# Sheet1.net
KiCad netlist of a schematic drawn in Altium Designer
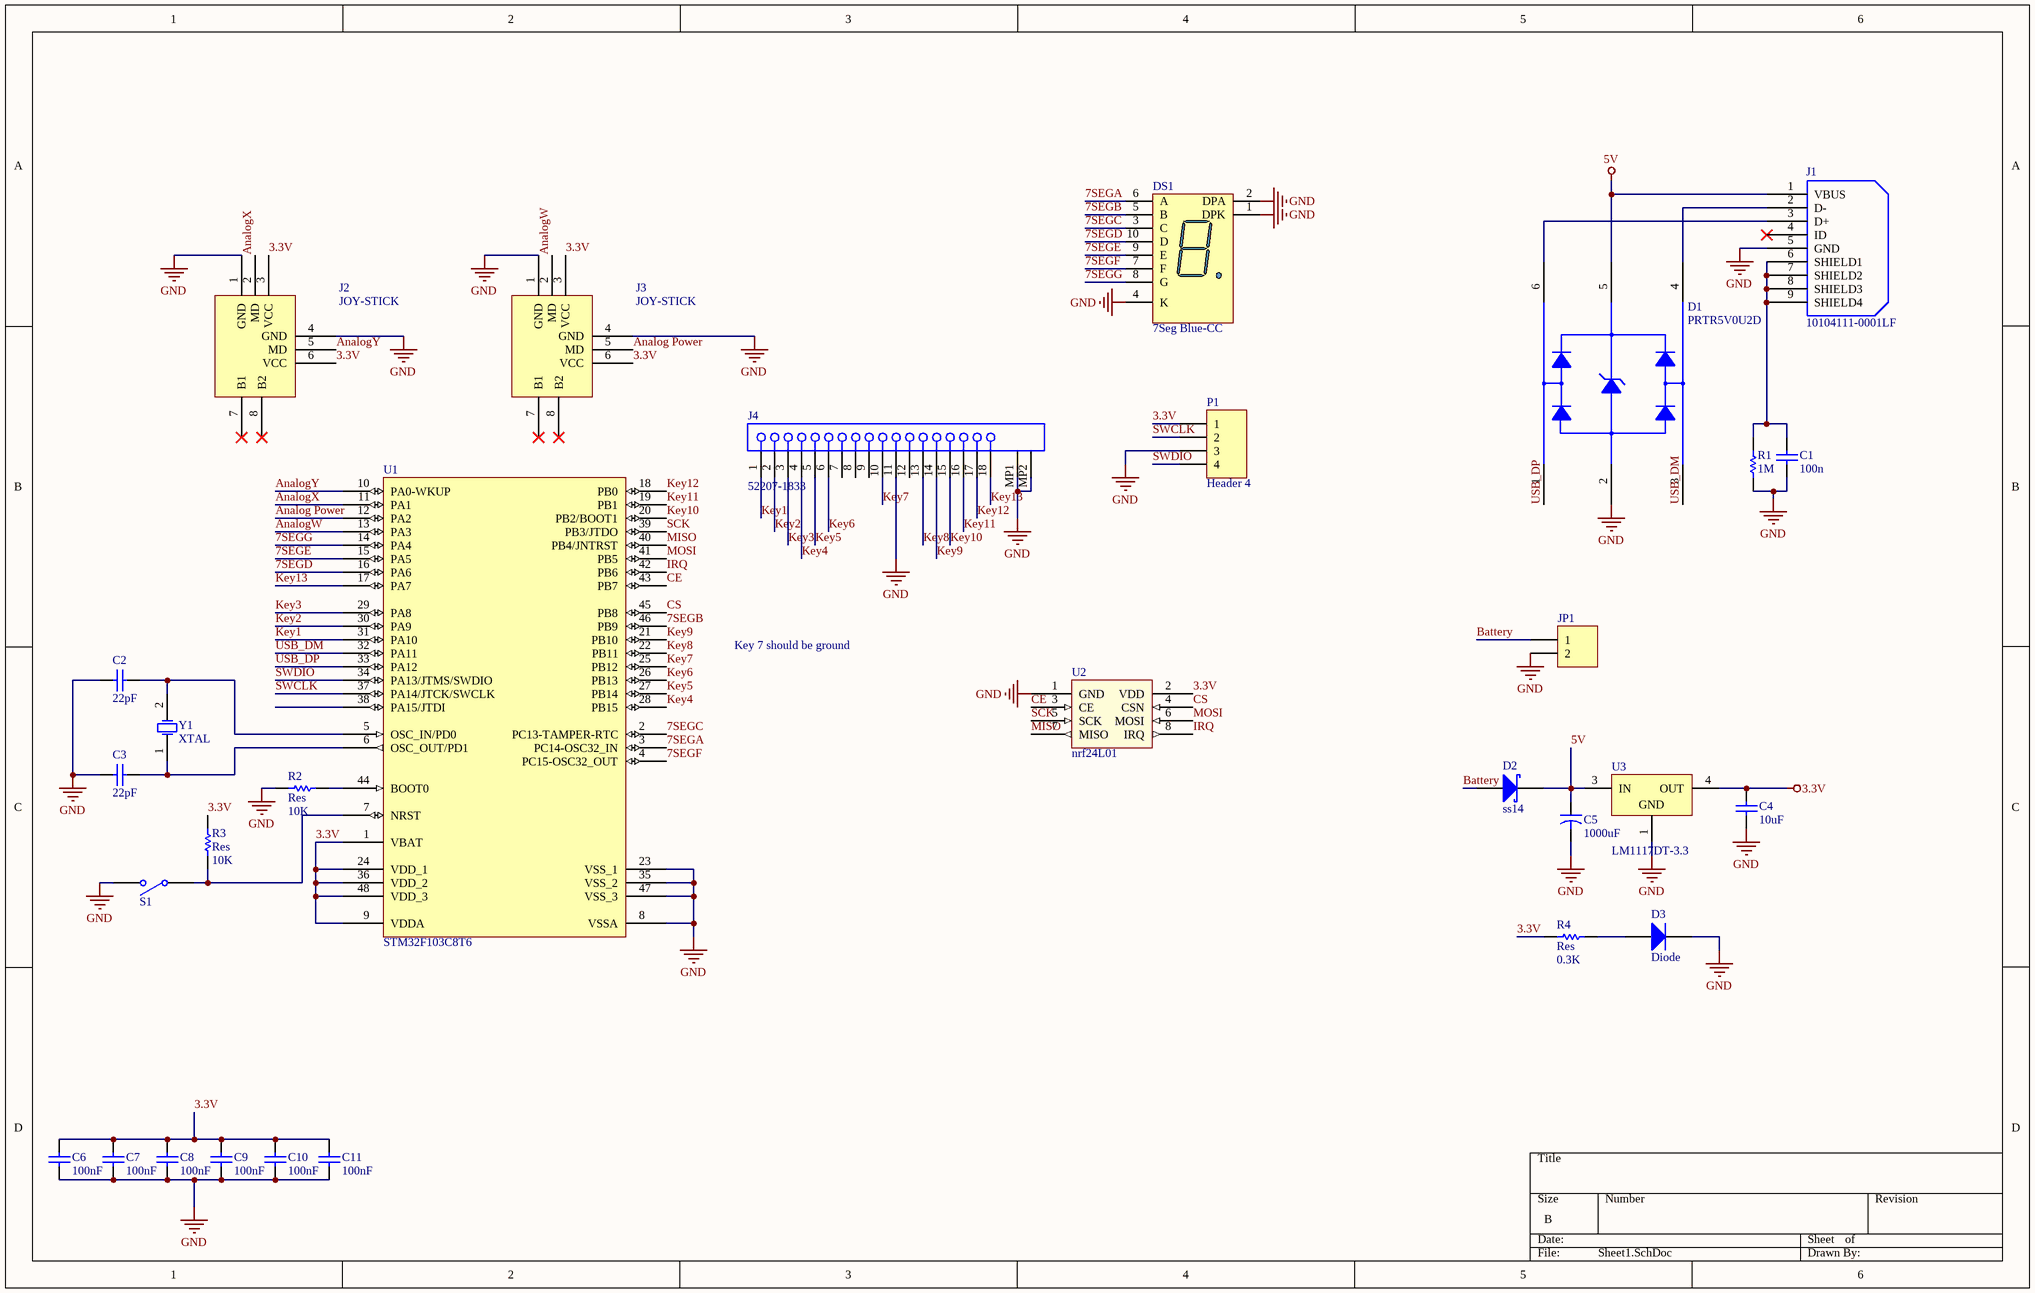
[diagram p0: Sheet1.SchDoc]

(export (version "E")
  (design (tool "Eeschema 10.0.6"))
  (components
    (comp (ref "C1")
      (value "100n")
      (footprint "6-0805_N")
      (description "Capacitor")
      (fields (field (name "PUBLISHER") "Altium Limited"))
      (libsource (lib "Miscellaneous Devices") (part "Cap"))
    )
    (comp (ref "C2")
      (value "22pF")
      (footprint "2012[0805]")
      (description "Capacitor")
      (fields (field (name "Comment") "Cap_UP") (field (name "PUBLISHER") "Altium Limited"))
      (libsource (lib "KN2CLib") (part "Cap_UP"))
    )
    (comp (ref "C3")
      (value "22pF")
      (footprint "2012[0805]")
      (description "Capacitor")
      (fields (field (name "Comment") "Cap_UP") (field (name "PUBLISHER") "Altium Limited"))
      (libsource (lib "KN2CLib") (part "Cap_UP"))
    )
    (comp (ref "C4")
      (value "10uF")
      (footprint "2012[0805]")
      (description "Capacitor")
      (fields (field (name "Comment") "Cap_UP") (field (name "PUBLISHER") "Altium Limited"))
      (libsource (lib "KN2CLib") (part "Cap_UP"))
    )
    (comp (ref "C5")
      (value "1000uF")
      (footprint "7343")
      (description "Capacitor")
      (fields (field (name "Comment") "Cap_El") (field (name "PUBLISHER") "Altium Limited"))
      (libsource (lib "KN2CLib") (part "Cap_El"))
    )
    (comp (ref "C6")
      (value "100nF")
      (footprint "2012[0805]")
      (description "Capacitor")
      (fields (field (name "Comment") "Cap_UP") (field (name "PUBLISHER") "Altium Limited"))
      (libsource (lib "KN2CLib") (part "Cap_UP"))
    )
    (comp (ref "C7")
      (value "100nF")
      (footprint "2012[0805]")
      (description "Capacitor")
      (fields (field (name "Comment") "Cap_UP") (field (name "PUBLISHER") "Altium Limited"))
      (libsource (lib "KN2CLib") (part "Cap_UP"))
    )
    (comp (ref "C8")
      (value "100nF")
      (footprint "2012[0805]")
      (description "Capacitor")
      (fields (field (name "Comment") "Cap_UP") (field (name "PUBLISHER") "Altium Limited"))
      (libsource (lib "KN2CLib") (part "Cap_UP"))
    )
    (comp (ref "C9")
      (value "100nF")
      (footprint "2012[0805]")
      (description "Capacitor")
      (fields (field (name "Comment") "Cap_UP") (field (name "PUBLISHER") "Altium Limited"))
      (libsource (lib "KN2CLib") (part "Cap_UP"))
    )
    (comp (ref "C10")
      (value "100nF")
      (footprint "2012[0805]")
      (description "Capacitor")
      (fields (field (name "Comment") "Cap_UP") (field (name "PUBLISHER") "Altium Limited"))
      (libsource (lib "KN2CLib") (part "Cap_UP"))
    )
    (comp (ref "C11")
      (value "100nF")
      (footprint "2012[0805]")
      (description "Capacitor")
      (fields (field (name "Comment") "Cap_UP") (field (name "PUBLISHER") "Altium Limited"))
      (libsource (lib "KN2CLib") (part "Cap_UP"))
    )
    (comp (ref "D1")
      (value "PRTR5V0U2D")
      (footprint "PRTR5V0U2D")
      (description "Double rail-to-rail USB ESD protection diode")
      (fields (field (name "MANUFACTURER") "Philips") (field (name "MPN") "PRTR5V0U2X"))
      (libsource (lib "KN2CLib") (part "PRTR5V0U2D"))
    )
    (comp (ref "D2")
      (value "ss14")
      (footprint "US1m")
      (description "Schottky Diode")
      (fields (field (name "PUBLISHER") "Altium Limited"))
      (libsource (lib "Miscellaneous Devices") (part "D Schottky"))
    )
    (comp (ref "D3")
      (value "Diode")
      (footprint "2012[0805]")
      (description "1 Amp General Purpose Rectifier")
      (fields (field (name "PUBLISHER") "Altium Limited"))
      (libsource (lib "KN2CLib") (part "Diode"))
    )
    (comp (ref "DS1")
      (value "7Seg Blue-CC")
      (footprint "7Segment Small")
      (description "14.2 mm General Purpose Blue 7-Segment Display: CC, RH DP, Gray Surface")
      (fields (field (name "PUBLISHER") "Altium Limited"))
      (libsource (lib "KN2CLib") (part "7Seg Blue-CC_1"))
    )
    (comp (ref "J1")
      (value "10104111-0001LF")
      (footprint "USB_MINI")
      (description "Micro USB AB Connector")
      (fields (field (name "MANUFACTURER") "FCI") (field (name "Comment") "USB_AB"))
      (libsource (lib "KN2CLib") (part "USB_AB"))
    )
    (comp (ref "J2")
      (value "JOY-STICK")
      (footprint "JOY STICK")
      (libsource (lib "KN2CLib") (part "JOY STICK"))
    )
    (comp (ref "J3")
      (value "JOY-STICK")
      (footprint "JOY STICK")
      (libsource (lib "KN2CLib") (part "JOY STICK"))
    )
    (comp (ref "J4")
      (value "52207-1833")
      (footprint "MOLX-52207-1833")
      (fields (field (name "MANUFACTURER") "Molex"))
      (libsource (lib "Molex FFC - FPC Connectors (SMT)") (part "52207-1833"))
    )
    (comp (ref "JP1")
      (value "Header 2")
      (footprint "HDR1X2A")
      (description "Header, 2-Pin")
      (fields (field (name "PUBLISHER") "Altium Limited"))
      (libsource (lib "KN2CLib") (part "Header 2"))
    )
    (comp (ref "P1")
      (value "Header 4")
      (footprint "HDR1X4")
      (description "Header, 4-Pin")
      (fields (field (name "PUBLISHER") "Altium Limited"))
      (libsource (lib "Miscellaneous Connectors") (part "Header 4"))
    )
    (comp (ref "R1")
      (value "1M")
      (footprint "2012[0805]")
      (description "Semiconductor Resistor")
      (fields (field (name "PUBLISHER") "Altium Limited"))
      (libsource (lib "KN2CLib") (part "Res"))
    )
    (comp (ref "R2")
      (value "Res")
      (footprint "2012[0805]")
      (description "Semiconductor Resistor")
      (fields (field (name "ALTIUM_VALUE") "10K") (field (name "PUBLISHER") "Altium Limited"))
      (libsource (lib "KN2CLib") (part "Res"))
    )
    (comp (ref "R3")
      (value "Res")
      (footprint "2012[0805]")
      (description "Semiconductor Resistor")
      (fields (field (name "ALTIUM_VALUE") "10K") (field (name "PUBLISHER") "Altium Limited"))
      (libsource (lib "KN2CLib") (part "Res"))
    )
    (comp (ref "R4")
      (value "Res")
      (footprint "2012[0805]")
      (description "Semiconductor Resistor")
      (fields (field (name "ALTIUM_VALUE") "0.3K") (field (name "PUBLISHER") "Altium Limited"))
      (libsource (lib "KN2CLib") (part "Res"))
    )
    (comp (ref "S1")
      (value "SW-SPST")
      (footprint "SW-SMD")
      (description "Single-Pole, Single-Throw Switch")
      (fields (field (name "PUBLISHER") "Altium Limited"))
      (libsource (lib "KN2CLib") (part "SW-SPST"))
    )
    (comp (ref "U1")
      (value "STM32F103C8T6")
      (footprint "LQFP48_N")
      (description "STM32 ARM-based 32-bit MCU with 64 Kbytes Flash, 48-pin LQFP, Industrial Temperature")
      (fields (field (name "PUBLISHER") "Altium Limited"))
      (libsource (lib "ST Microcontroller 32-Bit STM32") (part "STM32F103C8T6"))
    )
    (comp (ref "U2") (value "nrf24L01") (footprint "NRF24L01") (libsource (lib "KN2CLib") (part "nrf24L01")))
    (comp (ref "U3")
      (value "LM1117DT-3.3")
      (footprint "SOT223")
      (description "800mA Low-Dropout Linear Regulator, 3-pin TO-252")
      (fields
        (field (name "MANUFACTURER") "National Semiconductor")
        (field (name "PUBLISHER") "Altium Limited")
      )
      (libsource (lib "NSC LDO") (part "LM1117DT-3.3"))
    )
    (comp (ref "Y1")
      (value "XTAL")
      (footprint "R38")
      (description "Crystal Oscillator")
      (fields (field (name "PUBLISHER") "Altium Limited"))
      (libsource (lib "KN2CLib") (part "XTAL"))
    )
  )
  (nets
    (net (code "1") (name "/7SEGA") (class "Default")
      (node (ref "DS1") (pin "6") (pinfunction "A_6") (pintype "passive"))
      (node (ref "U1") (pin "3") (pinfunction "PC14-OSC32_IN_3") (pintype "bidirectional"))
    )
    (net (code "2") (name "/7SEGB") (class "Default")
      (node (ref "DS1") (pin "5") (pinfunction "B_5") (pintype "passive"))
      (node (ref "U1") (pin "46") (pinfunction "PB9_46") (pintype "bidirectional"))
    )
    (net (code "3") (name "/7SEGC") (class "Default")
      (node (ref "DS1") (pin "3") (pinfunction "C_3") (pintype "passive"))
      (node (ref "U1") (pin "2") (pinfunction "PC13-TAMPER-RTC_2") (pintype "bidirectional"))
    )
    (net (code "4") (name "/7SEGD") (class "Default")
      (node (ref "DS1") (pin "10") (pinfunction "D_10") (pintype "passive"))
      (node (ref "U1") (pin "16") (pinfunction "PA6_16") (pintype "bidirectional"))
    )
    (net (code "5") (name "/7SEGE") (class "Default")
      (node (ref "DS1") (pin "9") (pinfunction "E_9") (pintype "passive"))
      (node (ref "U1") (pin "15") (pinfunction "PA5_15") (pintype "bidirectional"))
    )
    (net (code "6") (name "/7SEGF") (class "Default")
      (node (ref "DS1") (pin "7") (pinfunction "F_7") (pintype "passive"))
      (node (ref "U1") (pin "4") (pinfunction "PC15-OSC32_OUT_4") (pintype "bidirectional"))
    )
    (net (code "7") (name "/7SEGG") (class "Default")
      (node (ref "DS1") (pin "8") (pinfunction "G_8") (pintype "passive"))
      (node (ref "U1") (pin "14") (pinfunction "PA4_14") (pintype "bidirectional"))
    )
    (net (code "8") (name "/Analog Power") (class "Default")
      (node (ref "J3") (pin "5") (pinfunction "MD_5") (pintype "passive"))
      (node (ref "U1") (pin "12") (pinfunction "PA2_12") (pintype "bidirectional"))
    )
    (net (code "9") (name "/AnalogW") (class "Default")
      (node (ref "J3") (pin "2") (pinfunction "MD_2") (pintype "passive"))
      (node (ref "U1") (pin "13") (pinfunction "PA3_13") (pintype "bidirectional"))
    )
    (net (code "10") (name "/AnalogX") (class "Default")
      (node (ref "J2") (pin "2") (pinfunction "MD_2") (pintype "passive"))
      (node (ref "U1") (pin "11") (pinfunction "PA1_11") (pintype "bidirectional"))
    )
    (net (code "11") (name "/AnalogY") (class "Default")
      (node (ref "J2") (pin "5") (pinfunction "MD_5") (pintype "passive"))
      (node (ref "U1") (pin "10") (pinfunction "PA0-WKUP_10") (pintype "bidirectional"))
    )
    (net (code "12") (name "/Battery") (class "Default")
      (node (ref "D2") (pin "1") (pinfunction "A_1") (pintype "passive"))
      (node (ref "JP1") (pin "1") (pinfunction "1_1") (pintype "passive"))
    )
    (net (code "13") (name "/CE") (class "Default")
      (node (ref "U1") (pin "43") (pinfunction "PB7_43") (pintype "bidirectional"))
      (node (ref "U2") (pin "3") (pinfunction "CE_3") (pintype "input"))
    )
    (net (code "14") (name "/CS") (class "Default")
      (node (ref "U1") (pin "45") (pinfunction "PB8_45") (pintype "bidirectional"))
      (node (ref "U2") (pin "4") (pinfunction "CSN_4") (pintype "input"))
    )
    (net (code "15") (name "/IRQ") (class "Default")
      (node (ref "U1") (pin "42") (pinfunction "PB6_42") (pintype "bidirectional"))
      (node (ref "U2") (pin "8") (pinfunction "IRQ_8") (pintype "output"))
    )
    (net (code "16") (name "/Key1") (class "Default")
      (node (ref "J4") (pin "1") (pinfunction "1_1") (pintype "passive"))
      (node (ref "U1") (pin "31") (pinfunction "PA10_31") (pintype "bidirectional"))
    )
    (net (code "17") (name "/Key2") (class "Default")
      (node (ref "J4") (pin "2") (pinfunction "2_2") (pintype "passive"))
      (node (ref "U1") (pin "30") (pinfunction "PA9_30") (pintype "bidirectional"))
    )
    (net (code "18") (name "/Key3") (class "Default")
      (node (ref "J4") (pin "3") (pinfunction "3_3") (pintype "passive"))
      (node (ref "U1") (pin "29") (pinfunction "PA8_29") (pintype "bidirectional"))
    )
    (net (code "19") (name "/Key4") (class "Default")
      (node (ref "J4") (pin "4") (pinfunction "4_4") (pintype "passive"))
      (node (ref "U1") (pin "28") (pinfunction "PB15_28") (pintype "bidirectional"))
    )
    (net (code "20") (name "/Key5") (class "Default")
      (node (ref "J4") (pin "5") (pinfunction "5_5") (pintype "passive"))
      (node (ref "U1") (pin "27") (pinfunction "PB14_27") (pintype "bidirectional"))
    )
    (net (code "21") (name "/Key6") (class "Default")
      (node (ref "J4") (pin "6") (pinfunction "6_6") (pintype "passive"))
      (node (ref "U1") (pin "26") (pinfunction "PB13_26") (pintype "bidirectional"))
    )
    (net (code "22") (name "/Key7") (class "Default")
      (node (ref "J4") (pin "10") (pinfunction "10_10") (pintype "passive"))
      (node (ref "U1") (pin "25") (pinfunction "PB12_25") (pintype "bidirectional"))
    )
    (net (code "23") (name "/Key8") (class "Default")
      (node (ref "J4") (pin "13") (pinfunction "13_13") (pintype "passive"))
      (node (ref "U1") (pin "22") (pinfunction "PB11_22") (pintype "bidirectional"))
    )
    (net (code "24") (name "/Key9") (class "Default")
      (node (ref "J4") (pin "14") (pinfunction "14_14") (pintype "passive"))
      (node (ref "U1") (pin "21") (pinfunction "PB10_21") (pintype "bidirectional"))
    )
    (net (code "25") (name "/Key10") (class "Default")
      (node (ref "J4") (pin "15") (pinfunction "15_15") (pintype "passive"))
      (node (ref "U1") (pin "20") (pinfunction "PB2/BOOT1_20") (pintype "bidirectional"))
    )
    (net (code "26") (name "/Key11") (class "Default")
      (node (ref "J4") (pin "16") (pinfunction "16_16") (pintype "passive"))
      (node (ref "U1") (pin "19") (pinfunction "PB1_19") (pintype "bidirectional"))
    )
    (net (code "27") (name "/Key12") (class "Default")
      (node (ref "J4") (pin "17") (pinfunction "17_17") (pintype "passive"))
      (node (ref "U1") (pin "18") (pinfunction "PB0_18") (pintype "bidirectional"))
    )
    (net (code "28") (name "/Key13") (class "Default")
      (node (ref "J4") (pin "18") (pinfunction "18_18") (pintype "passive"))
      (node (ref "U1") (pin "17") (pinfunction "PA7_17") (pintype "bidirectional"))
    )
    (net (code "29") (name "/MISO") (class "Default")
      (node (ref "U1") (pin "40") (pinfunction "PB4/JNTRST_40") (pintype "bidirectional"))
      (node (ref "U2") (pin "7") (pinfunction "MISO_7") (pintype "output"))
    )
    (net (code "30") (name "/MOSI") (class "Default")
      (node (ref "U1") (pin "41") (pinfunction "PB5_41") (pintype "bidirectional"))
      (node (ref "U2") (pin "6") (pinfunction "MOSI_6") (pintype "input"))
    )
    (net (code "31") (name "/SCK") (class "Default")
      (node (ref "U1") (pin "39") (pinfunction "PB3/JTDO_39") (pintype "bidirectional"))
      (node (ref "U2") (pin "5") (pinfunction "SCK_5") (pintype "input"))
    )
    (net (code "32") (name "/SWCLK") (class "Default")
      (node (ref "P1") (pin "2") (pinfunction "2_2") (pintype "passive"))
      (node (ref "U1") (pin "37") (pinfunction "PA14/JTCK/SWCLK_37") (pintype "bidirectional"))
    )
    (net (code "33") (name "/SWDIO") (class "Default")
      (node (ref "P1") (pin "4") (pinfunction "4_4") (pintype "passive"))
      (node (ref "U1") (pin "34") (pinfunction "PA13/JTMS/SWDIO_34") (pintype "bidirectional"))
    )
    (net (code "34") (name "/USB_DM") (class "Default")
      (node (ref "D1") (pin "3") (pinfunction "I/O2_3") (pintype "passive"))
      (node (ref "U1") (pin "32") (pinfunction "PA11_32") (pintype "bidirectional"))
    )
    (net (code "35") (name "/USB_DP") (class "Default")
      (node (ref "D1") (pin "1") (pinfunction "I/O_1_1") (pintype "passive"))
      (node (ref "U1") (pin "33") (pinfunction "PA12_33") (pintype "bidirectional"))
    )
    (net (code "36") (name "3.3V") (class "Default")
      (node (ref "C10") (pin "2") (pinfunction "2_2") (pintype "passive"))
      (node (ref "C11") (pin "2") (pinfunction "2_2") (pintype "passive"))
      (node (ref "C4") (pin "2") (pinfunction "2_2") (pintype "passive"))
      (node (ref "C6") (pin "2") (pinfunction "2_2") (pintype "passive"))
      (node (ref "C7") (pin "2") (pinfunction "2_2") (pintype "passive"))
      (node (ref "C8") (pin "2") (pinfunction "2_2") (pintype "passive"))
      (node (ref "C9") (pin "2") (pinfunction "2_2") (pintype "passive"))
      (node (ref "J2") (pin "3") (pinfunction "VCC_3") (pintype "passive"))
      (node (ref "J2") (pin "6") (pinfunction "VCC_6") (pintype "passive"))
      (node (ref "J3") (pin "3") (pinfunction "VCC_3") (pintype "passive"))
      (node (ref "J3") (pin "6") (pinfunction "VCC_6") (pintype "passive"))
      (node (ref "P1") (pin "1") (pinfunction "1_1") (pintype "passive"))
      (node (ref "R3") (pin "2") (pinfunction "2_2") (pintype "passive"))
      (node (ref "R4") (pin "1") (pinfunction "1_1") (pintype "passive"))
      (node (ref "U1") (pin "1") (pinfunction "VBAT_1") (pintype "power_in"))
      (node (ref "U1") (pin "24") (pinfunction "VDD_1_24") (pintype "power_in"))
      (node (ref "U1") (pin "36") (pinfunction "VDD_2_36") (pintype "power_in"))
      (node (ref "U1") (pin "48") (pinfunction "VDD_3_48") (pintype "power_in"))
      (node (ref "U1") (pin "9") (pinfunction "VDDA_9") (pintype "power_in"))
      (node (ref "U2") (pin "2") (pinfunction "VDD_2") (pintype "power_in"))
      (node (ref "U3") (pin "4") (pinfunction "OUT_4") (pintype "power_in"))
    )
    (net (code "37") (name "5V") (class "Default")
      (node (ref "C5") (pin "1") (pinfunction "1_1") (pintype "passive"))
      (node (ref "D1") (pin "5") (pinfunction "VCC_5") (pintype "passive"))
      (node (ref "D2") (pin "2") (pinfunction "K_2") (pintype "passive"))
      (node (ref "J1") (pin "1") (pinfunction "VBUS_1") (pintype "passive"))
      (node (ref "U3") (pin "3") (pinfunction "IN_3") (pintype "power_in"))
    )
    (net (code "38") (name "GND") (class "Default")
      (node (ref "C1") (pin "1") (pinfunction "1_1") (pintype "passive"))
      (node (ref "C10") (pin "1") (pinfunction "1_1") (pintype "passive"))
      (node (ref "C11") (pin "1") (pinfunction "1_1") (pintype "passive"))
      (node (ref "C2") (pin "1") (pinfunction "1_1") (pintype "passive"))
      (node (ref "C3") (pin "1") (pinfunction "1_1") (pintype "passive"))
      (node (ref "C4") (pin "1") (pinfunction "1_1") (pintype "passive"))
      (node (ref "C5") (pin "2") (pinfunction "2_2") (pintype "passive"))
      (node (ref "C6") (pin "1") (pinfunction "1_1") (pintype "passive"))
      (node (ref "C7") (pin "1") (pinfunction "1_1") (pintype "passive"))
      (node (ref "C8") (pin "1") (pinfunction "1_1") (pintype "passive"))
      (node (ref "C9") (pin "1") (pinfunction "1_1") (pintype "passive"))
      (node (ref "D1") (pin "2") (pinfunction "GND_2") (pintype "passive"))
      (node (ref "D3") (pin "2") (pinfunction "K_2") (pintype "passive"))
      (node (ref "DS1") (pin "1") (pinfunction "DPK_1") (pintype "passive"))
      (node (ref "DS1") (pin "2") (pinfunction "DPA_2") (pintype "passive"))
      (node (ref "DS1") (pin "4") (pinfunction "K_4") (pintype "passive"))
      (node (ref "J1") (pin "5") (pinfunction "GND_5") (pintype "passive"))
      (node (ref "J2") (pin "1") (pinfunction "GND_1") (pintype "passive"))
      (node (ref "J2") (pin "4") (pinfunction "GND_4") (pintype "passive"))
      (node (ref "J3") (pin "1") (pinfunction "GND_1") (pintype "passive"))
      (node (ref "J3") (pin "4") (pinfunction "GND_4") (pintype "passive"))
      (node (ref "J4") (pin "11") (pinfunction "11_11") (pintype "passive"))
      (node (ref "J4") (pin "MP1") (pinfunction "MP1_MP1") (pintype "passive"))
      (node (ref "J4") (pin "MP2") (pinfunction "MP2_MP2") (pintype "passive"))
      (node (ref "JP1") (pin "2") (pinfunction "2_2") (pintype "passive"))
      (node (ref "P1") (pin "3") (pinfunction "3_3") (pintype "passive"))
      (node (ref "R1") (pin "1") (pinfunction "1_1") (pintype "passive"))
      (node (ref "R2") (pin "1") (pinfunction "1_1") (pintype "passive"))
      (node (ref "S1") (pin "2") (pinfunction "NO_2") (pintype "passive"))
      (node (ref "U1") (pin "23") (pinfunction "VSS_1_23") (pintype "power_in"))
      (node (ref "U1") (pin "35") (pinfunction "VSS_2_35") (pintype "power_in"))
      (node (ref "U1") (pin "47") (pinfunction "VSS_3_47") (pintype "power_in"))
      (node (ref "U1") (pin "8") (pinfunction "VSSA_8") (pintype "power_in"))
      (node (ref "U2") (pin "1") (pinfunction "GND_1") (pintype "power_in"))
      (node (ref "U3") (pin "1") (pinfunction "GND_1") (pintype "power_in"))
    )
    (net (code "39") (name "Net-(D1-I{slash}O1)") (class "Default")
      (node (ref "D1") (pin "6") (pinfunction "I/O1_6") (pintype "passive"))
      (node (ref "J1") (pin "3") (pinfunction "D+_3") (pintype "passive"))
    )
    (net (code "40") (name "Net-(D3-A)") (class "Default")
      (node (ref "D3") (pin "1") (pinfunction "A_1") (pintype "passive"))
      (node (ref "R4") (pin "2") (pinfunction "2_2") (pintype "passive"))
    )
    (net (code "41") (name "Net-(J1-D-)") (class "Default")
      (node (ref "D1") (pin "4") (pinfunction "I/O2_4") (pintype "passive"))
      (node (ref "J1") (pin "2") (pinfunction "D-_2") (pintype "passive"))
    )
    (net (code "42") (name "Net-(J1-SHIELD1)") (class "Default")
      (node (ref "C1") (pin "2") (pinfunction "2_2") (pintype "passive"))
      (node (ref "J1") (pin "6") (pinfunction "SHIELD1_6") (pintype "passive"))
      (node (ref "J1") (pin "7") (pinfunction "SHIELD2_7") (pintype "passive"))
      (node (ref "J1") (pin "8") (pinfunction "SHIELD3_8") (pintype "passive"))
      (node (ref "J1") (pin "9") (pinfunction "SHIELD4_9") (pintype "passive"))
      (node (ref "R1") (pin "2") (pinfunction "2_2") (pintype "passive"))
    )
    (net (code "43") (name "Net-(S1-COMMON)") (class "Default")
      (node (ref "R3") (pin "1") (pinfunction "1_1") (pintype "passive"))
      (node (ref "S1") (pin "1") (pinfunction "COMMON_1") (pintype "passive"))
      (node (ref "U1") (pin "7") (pinfunction "NRST_7") (pintype "bidirectional"))
    )
    (net (code "44") (name "Net-(U1-BOOT0)") (class "Default")
      (node (ref "R2") (pin "2") (pinfunction "2_2") (pintype "passive"))
      (node (ref "U1") (pin "44") (pinfunction "BOOT0_44") (pintype "input"))
    )
    (net (code "45") (name "Net-(U1-OSC_IN{slash}PD0)") (class "Default")
      (node (ref "C2") (pin "2") (pinfunction "2_2") (pintype "passive"))
      (node (ref "U1") (pin "5") (pinfunction "OSC_IN/PD0_5") (pintype "input"))
      (node (ref "Y1") (pin "2") (pinfunction "OSC2_2") (pintype "passive"))
    )
    (net (code "46") (name "Net-(U1-OSC_OUT{slash}PD1)") (class "Default")
      (node (ref "C3") (pin "2") (pinfunction "2_2") (pintype "passive"))
      (node (ref "U1") (pin "6") (pinfunction "OSC_OUT/PD1_6") (pintype "output"))
      (node (ref "Y1") (pin "1") (pinfunction "OSC1_1") (pintype "passive"))
    )
    (net (code "47") (name "unconnected-(J1-ID-Pad4)") (class "Default")
      (node (ref "J1") (pin "4") (pinfunction "ID_4") (pintype "passive+no_connect"))
    )
    (net (code "48") (name "unconnected-(J2-B1-Pad7)") (class "Default")
      (node (ref "J2") (pin "7") (pinfunction "B1_7") (pintype "passive+no_connect"))
    )
    (net (code "49") (name "unconnected-(J2-B2-Pad8)") (class "Default")
      (node (ref "J2") (pin "8") (pinfunction "B2_8") (pintype "passive+no_connect"))
    )
    (net (code "50") (name "unconnected-(J3-B1-Pad7)") (class "Default")
      (node (ref "J3") (pin "7") (pinfunction "B1_7") (pintype "passive+no_connect"))
    )
    (net (code "51") (name "unconnected-(J3-B2-Pad8)") (class "Default")
      (node (ref "J3") (pin "8") (pinfunction "B2_8") (pintype "passive+no_connect"))
    )
    (net (code "52") (name "unconnected-(J4-Pad7)") (class "Default")
      (node (ref "J4") (pin "7") (pinfunction "7_7") (pintype "passive"))
    )
    (net (code "53") (name "unconnected-(J4-Pad8)") (class "Default")
      (node (ref "J4") (pin "8") (pinfunction "8_8") (pintype "passive"))
    )
    (net (code "54") (name "unconnected-(J4-Pad9)") (class "Default")
      (node (ref "J4") (pin "9") (pinfunction "9_9") (pintype "passive"))
    )
    (net (code "55") (name "unconnected-(J4-Pad12)") (class "Default")
      (node (ref "J4") (pin "12") (pinfunction "12_12") (pintype "passive"))
    )
    (net (code "56") (name "unconnected-(U1-PA15{slash}JTDI-Pad38)") (class "Default")
      (node (ref "U1") (pin "38") (pinfunction "PA15/JTDI_38") (pintype "bidirectional"))
    )
  )
)
